# keypad-encoder.net
KiCad netlist of a schematic drawn in EAGLE
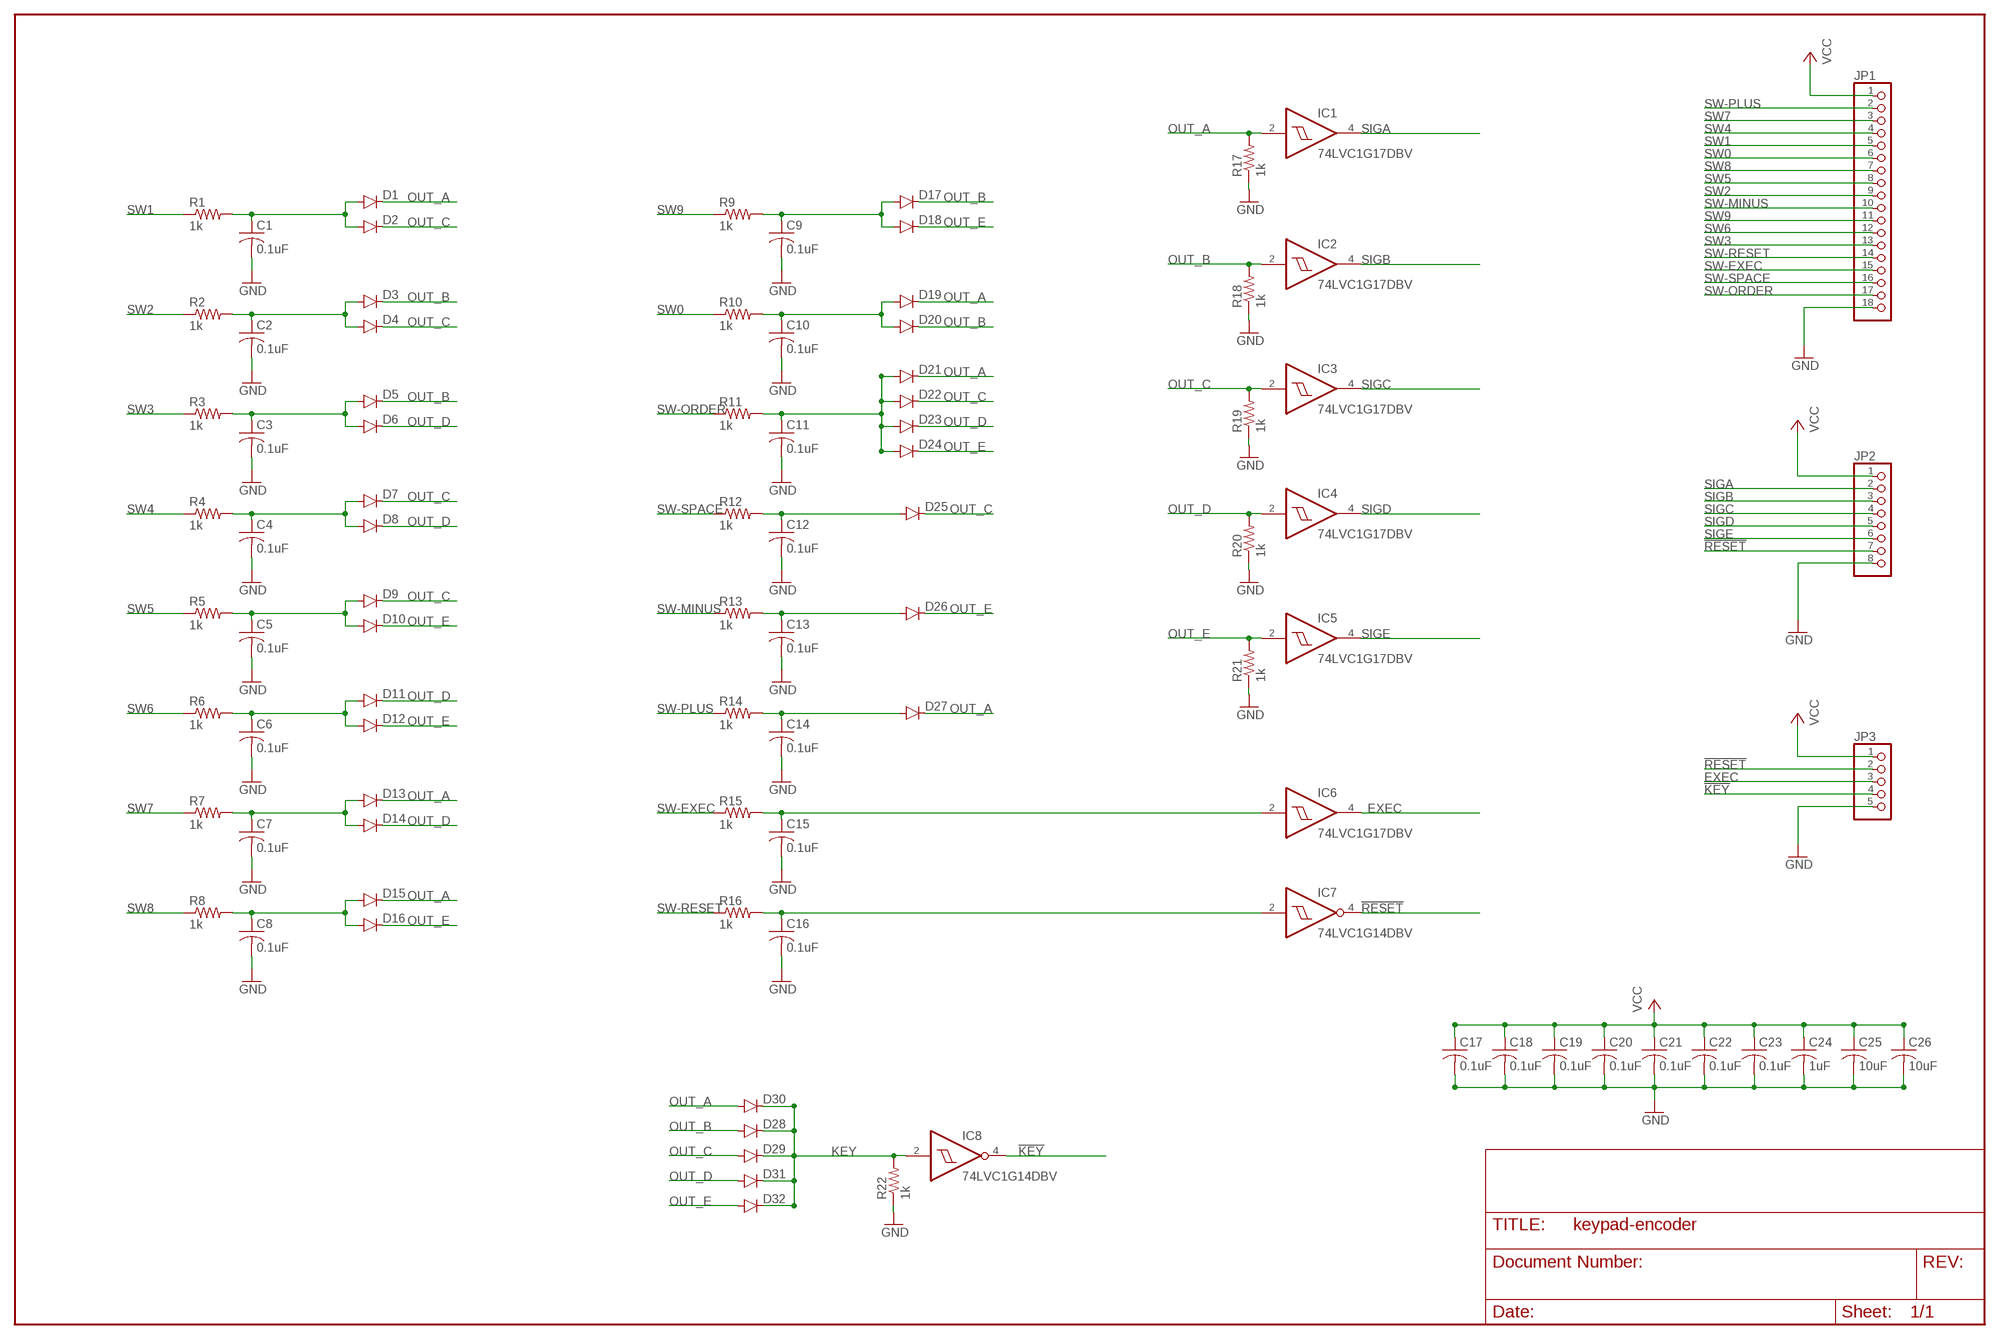
[diagram p0: schematic, sheet 1]

(export (version "E")
  (design (tool "Eeschema 10.0.6"))
  (components
    (comp (ref "C1")
      (value "0.1uF")
      (footprint "eagle-import:C0805")
      (libsource (lib "eagle-import") (part "C-USC0805"))
    )
    (comp (ref "C2")
      (value "0.1uF")
      (footprint "eagle-import:C0805")
      (libsource (lib "eagle-import") (part "C-USC0805"))
    )
    (comp (ref "C3")
      (value "0.1uF")
      (footprint "eagle-import:C0805")
      (libsource (lib "eagle-import") (part "C-USC0805"))
    )
    (comp (ref "C4")
      (value "0.1uF")
      (footprint "eagle-import:C0805")
      (libsource (lib "eagle-import") (part "C-USC0805"))
    )
    (comp (ref "C5")
      (value "0.1uF")
      (footprint "eagle-import:C0805")
      (libsource (lib "eagle-import") (part "C-USC0805"))
    )
    (comp (ref "C6")
      (value "0.1uF")
      (footprint "eagle-import:C0805")
      (libsource (lib "eagle-import") (part "C-USC0805"))
    )
    (comp (ref "C7")
      (value "0.1uF")
      (footprint "eagle-import:C0805")
      (libsource (lib "eagle-import") (part "C-USC0805"))
    )
    (comp (ref "C8")
      (value "0.1uF")
      (footprint "eagle-import:C0805")
      (libsource (lib "eagle-import") (part "C-USC0805"))
    )
    (comp (ref "C9")
      (value "0.1uF")
      (footprint "eagle-import:C0805")
      (libsource (lib "eagle-import") (part "C-USC0805"))
    )
    (comp (ref "C10")
      (value "0.1uF")
      (footprint "eagle-import:C0805")
      (libsource (lib "eagle-import") (part "C-USC0805"))
    )
    (comp (ref "C11")
      (value "0.1uF")
      (footprint "eagle-import:C0805")
      (libsource (lib "eagle-import") (part "C-USC0805"))
    )
    (comp (ref "C12")
      (value "0.1uF")
      (footprint "eagle-import:C0805")
      (libsource (lib "eagle-import") (part "C-USC0805"))
    )
    (comp (ref "C13")
      (value "0.1uF")
      (footprint "eagle-import:C0805")
      (libsource (lib "eagle-import") (part "C-USC0805"))
    )
    (comp (ref "C14")
      (value "0.1uF")
      (footprint "eagle-import:C0805")
      (libsource (lib "eagle-import") (part "C-USC0805"))
    )
    (comp (ref "C15")
      (value "0.1uF")
      (footprint "eagle-import:C0805")
      (libsource (lib "eagle-import") (part "C-USC0805"))
    )
    (comp (ref "C16")
      (value "0.1uF")
      (footprint "eagle-import:C0805")
      (libsource (lib "eagle-import") (part "C-USC0805"))
    )
    (comp (ref "C17")
      (value "0.1uF")
      (footprint "eagle-import:C0805")
      (libsource (lib "eagle-import") (part "C-USC0805"))
    )
    (comp (ref "C18")
      (value "0.1uF")
      (footprint "eagle-import:C0805")
      (libsource (lib "eagle-import") (part "C-USC0805"))
    )
    (comp (ref "C19")
      (value "0.1uF")
      (footprint "eagle-import:C0805")
      (libsource (lib "eagle-import") (part "C-USC0805"))
    )
    (comp (ref "C20")
      (value "0.1uF")
      (footprint "eagle-import:C0805")
      (libsource (lib "eagle-import") (part "C-USC0805"))
    )
    (comp (ref "C21")
      (value "0.1uF")
      (footprint "eagle-import:C0805")
      (libsource (lib "eagle-import") (part "C-USC0805"))
    )
    (comp (ref "C22")
      (value "0.1uF")
      (footprint "eagle-import:C0805")
      (libsource (lib "eagle-import") (part "C-USC0805"))
    )
    (comp (ref "C23")
      (value "0.1uF")
      (footprint "eagle-import:C0805")
      (libsource (lib "eagle-import") (part "C-USC0805"))
    )
    (comp (ref "C24")
      (value "1uF")
      (footprint "eagle-import:C0805")
      (libsource (lib "eagle-import") (part "C-USC0805"))
    )
    (comp (ref "C25")
      (value "10uF")
      (footprint "eagle-import:C0805")
      (libsource (lib "eagle-import") (part "C-USC0805"))
    )
    (comp (ref "C26")
      (value "10uF")
      (footprint "eagle-import:C0805")
      (libsource (lib "eagle-import") (part "C-USC0805"))
    )
    (comp (ref "D1")
      (value "DIODEPTH")
      (footprint "eagle-import:DIODE-1N4001")
      (libsource (lib "eagle-import") (part "DIODEPTH"))
    )
    (comp (ref "D2")
      (value "DIODEPTH")
      (footprint "eagle-import:DIODE-1N4001")
      (libsource (lib "eagle-import") (part "DIODEPTH"))
    )
    (comp (ref "D3")
      (value "DIODEPTH")
      (footprint "eagle-import:DIODE-1N4001")
      (libsource (lib "eagle-import") (part "DIODEPTH"))
    )
    (comp (ref "D4")
      (value "DIODEPTH")
      (footprint "eagle-import:DIODE-1N4001")
      (libsource (lib "eagle-import") (part "DIODEPTH"))
    )
    (comp (ref "D5")
      (value "DIODEPTH")
      (footprint "eagle-import:DIODE-1N4001")
      (libsource (lib "eagle-import") (part "DIODEPTH"))
    )
    (comp (ref "D6")
      (value "DIODEPTH")
      (footprint "eagle-import:DIODE-1N4001")
      (libsource (lib "eagle-import") (part "DIODEPTH"))
    )
    (comp (ref "D7")
      (value "DIODEPTH")
      (footprint "eagle-import:DIODE-1N4001")
      (libsource (lib "eagle-import") (part "DIODEPTH"))
    )
    (comp (ref "D8")
      (value "DIODEPTH")
      (footprint "eagle-import:DIODE-1N4001")
      (libsource (lib "eagle-import") (part "DIODEPTH"))
    )
    (comp (ref "D9")
      (value "DIODEPTH")
      (footprint "eagle-import:DIODE-1N4001")
      (libsource (lib "eagle-import") (part "DIODEPTH"))
    )
    (comp (ref "D10")
      (value "DIODEPTH")
      (footprint "eagle-import:DIODE-1N4001")
      (libsource (lib "eagle-import") (part "DIODEPTH"))
    )
    (comp (ref "D11")
      (value "DIODEPTH")
      (footprint "eagle-import:DIODE-1N4001")
      (libsource (lib "eagle-import") (part "DIODEPTH"))
    )
    (comp (ref "D12")
      (value "DIODEPTH")
      (footprint "eagle-import:DIODE-1N4001")
      (libsource (lib "eagle-import") (part "DIODEPTH"))
    )
    (comp (ref "D13")
      (value "DIODEPTH")
      (footprint "eagle-import:DIODE-1N4001")
      (libsource (lib "eagle-import") (part "DIODEPTH"))
    )
    (comp (ref "D14")
      (value "DIODEPTH")
      (footprint "eagle-import:DIODE-1N4001")
      (libsource (lib "eagle-import") (part "DIODEPTH"))
    )
    (comp (ref "D15")
      (value "DIODEPTH")
      (footprint "eagle-import:DIODE-1N4001")
      (libsource (lib "eagle-import") (part "DIODEPTH"))
    )
    (comp (ref "D16")
      (value "DIODEPTH")
      (footprint "eagle-import:DIODE-1N4001")
      (libsource (lib "eagle-import") (part "DIODEPTH"))
    )
    (comp (ref "D17")
      (value "DIODEPTH")
      (footprint "eagle-import:DIODE-1N4001")
      (libsource (lib "eagle-import") (part "DIODEPTH"))
    )
    (comp (ref "D18")
      (value "DIODEPTH")
      (footprint "eagle-import:DIODE-1N4001")
      (libsource (lib "eagle-import") (part "DIODEPTH"))
    )
    (comp (ref "D19")
      (value "DIODEPTH")
      (footprint "eagle-import:DIODE-1N4001")
      (libsource (lib "eagle-import") (part "DIODEPTH"))
    )
    (comp (ref "D20")
      (value "DIODEPTH")
      (footprint "eagle-import:DIODE-1N4001")
      (libsource (lib "eagle-import") (part "DIODEPTH"))
    )
    (comp (ref "D21")
      (value "DIODEPTH")
      (footprint "eagle-import:DIODE-1N4001")
      (libsource (lib "eagle-import") (part "DIODEPTH"))
    )
    (comp (ref "D22")
      (value "DIODEPTH")
      (footprint "eagle-import:DIODE-1N4001")
      (libsource (lib "eagle-import") (part "DIODEPTH"))
    )
    (comp (ref "D23")
      (value "DIODEPTH")
      (footprint "eagle-import:DIODE-1N4001")
      (libsource (lib "eagle-import") (part "DIODEPTH"))
    )
    (comp (ref "D24")
      (value "DIODEPTH")
      (footprint "eagle-import:DIODE-1N4001")
      (libsource (lib "eagle-import") (part "DIODEPTH"))
    )
    (comp (ref "D25")
      (value "DIODEPTH")
      (footprint "eagle-import:DIODE-1N4001")
      (libsource (lib "eagle-import") (part "DIODEPTH"))
    )
    (comp (ref "D26")
      (value "DIODEPTH")
      (footprint "eagle-import:DIODE-1N4001")
      (libsource (lib "eagle-import") (part "DIODEPTH"))
    )
    (comp (ref "D27")
      (value "DIODEPTH")
      (footprint "eagle-import:DIODE-1N4001")
      (libsource (lib "eagle-import") (part "DIODEPTH"))
    )
    (comp (ref "D28")
      (value "DIODEPTH")
      (footprint "eagle-import:DIODE-1N4001")
      (libsource (lib "eagle-import") (part "DIODEPTH"))
    )
    (comp (ref "D29")
      (value "DIODEPTH")
      (footprint "eagle-import:DIODE-1N4001")
      (libsource (lib "eagle-import") (part "DIODEPTH"))
    )
    (comp (ref "D30")
      (value "DIODEPTH")
      (footprint "eagle-import:DIODE-1N4001")
      (libsource (lib "eagle-import") (part "DIODEPTH"))
    )
    (comp (ref "D31")
      (value "DIODEPTH")
      (footprint "eagle-import:DIODE-1N4001")
      (libsource (lib "eagle-import") (part "DIODEPTH"))
    )
    (comp (ref "D32")
      (value "DIODEPTH")
      (footprint "eagle-import:DIODE-1N4001")
      (libsource (lib "eagle-import") (part "DIODEPTH"))
    )
    (comp (ref "IC1")
      (value "74LVC1G17DBV")
      (footprint "eagle-import:SOT23-5")
      (libsource (lib "eagle-import") (part "741G17DBVLVC"))
    )
    (comp (ref "IC2")
      (value "74LVC1G17DBV")
      (footprint "eagle-import:SOT23-5")
      (libsource (lib "eagle-import") (part "741G17DBVLVC"))
    )
    (comp (ref "IC3")
      (value "74LVC1G17DBV")
      (footprint "eagle-import:SOT23-5")
      (libsource (lib "eagle-import") (part "741G17DBVLVC"))
    )
    (comp (ref "IC4")
      (value "74LVC1G17DBV")
      (footprint "eagle-import:SOT23-5")
      (libsource (lib "eagle-import") (part "741G17DBVLVC"))
    )
    (comp (ref "IC5")
      (value "74LVC1G17DBV")
      (footprint "eagle-import:SOT23-5")
      (libsource (lib "eagle-import") (part "741G17DBVLVC"))
    )
    (comp (ref "IC6")
      (value "74LVC1G17DBV")
      (footprint "eagle-import:SOT23-5")
      (libsource (lib "eagle-import") (part "741G17DBVLVC"))
    )
    (comp (ref "IC7")
      (value "74LVC1G14DBV")
      (footprint "eagle-import:SOT23-5")
      (libsource (lib "eagle-import") (part "741G14DBVLVC"))
    )
    (comp (ref "IC8")
      (value "74LVC1G14DBV")
      (footprint "eagle-import:SOT23-5")
      (libsource (lib "eagle-import") (part "741G14DBVLVC"))
    )
    (comp (ref "JP1")
      (value "PINHD-1X18")
      (footprint "eagle-import:1X18")
      (libsource (lib "eagle-import") (part "PINHD-1X18"))
    )
    (comp (ref "JP2")
      (value "PINHD-1X8")
      (footprint "eagle-import:1X08")
      (libsource (lib "eagle-import") (part "PINHD-1X8"))
    )
    (comp (ref "JP3")
      (value "PINHD-1X5")
      (footprint "eagle-import:1X05")
      (libsource (lib "eagle-import") (part "PINHD-1X5"))
    )
    (comp (ref "R1")
      (value "1k")
      (footprint "eagle-import:R0805")
      (libsource (lib "eagle-import") (part "R-US_R0805"))
    )
    (comp (ref "R2")
      (value "1k")
      (footprint "eagle-import:R0805")
      (libsource (lib "eagle-import") (part "R-US_R0805"))
    )
    (comp (ref "R3")
      (value "1k")
      (footprint "eagle-import:R0805")
      (libsource (lib "eagle-import") (part "R-US_R0805"))
    )
    (comp (ref "R4")
      (value "1k")
      (footprint "eagle-import:R0805")
      (libsource (lib "eagle-import") (part "R-US_R0805"))
    )
    (comp (ref "R5")
      (value "1k")
      (footprint "eagle-import:R0805")
      (libsource (lib "eagle-import") (part "R-US_R0805"))
    )
    (comp (ref "R6")
      (value "1k")
      (footprint "eagle-import:R0805")
      (libsource (lib "eagle-import") (part "R-US_R0805"))
    )
    (comp (ref "R7")
      (value "1k")
      (footprint "eagle-import:R0805")
      (libsource (lib "eagle-import") (part "R-US_R0805"))
    )
    (comp (ref "R8")
      (value "1k")
      (footprint "eagle-import:R0805")
      (libsource (lib "eagle-import") (part "R-US_R0805"))
    )
    (comp (ref "R9")
      (value "1k")
      (footprint "eagle-import:R0805")
      (libsource (lib "eagle-import") (part "R-US_R0805"))
    )
    (comp (ref "R10")
      (value "1k")
      (footprint "eagle-import:R0805")
      (libsource (lib "eagle-import") (part "R-US_R0805"))
    )
    (comp (ref "R11")
      (value "1k")
      (footprint "eagle-import:R0805")
      (libsource (lib "eagle-import") (part "R-US_R0805"))
    )
    (comp (ref "R12")
      (value "1k")
      (footprint "eagle-import:R0805")
      (libsource (lib "eagle-import") (part "R-US_R0805"))
    )
    (comp (ref "R13")
      (value "1k")
      (footprint "eagle-import:R0805")
      (libsource (lib "eagle-import") (part "R-US_R0805"))
    )
    (comp (ref "R14")
      (value "1k")
      (footprint "eagle-import:R0805")
      (libsource (lib "eagle-import") (part "R-US_R0805"))
    )
    (comp (ref "R15")
      (value "1k")
      (footprint "eagle-import:R0805")
      (libsource (lib "eagle-import") (part "R-US_R0805"))
    )
    (comp (ref "R16")
      (value "1k")
      (footprint "eagle-import:R0805")
      (libsource (lib "eagle-import") (part "R-US_R0805"))
    )
    (comp (ref "R17")
      (value "1k")
      (footprint "eagle-import:R0805")
      (libsource (lib "eagle-import") (part "R-US_R0805"))
    )
    (comp (ref "R18")
      (value "1k")
      (footprint "eagle-import:R0805")
      (libsource (lib "eagle-import") (part "R-US_R0805"))
    )
    (comp (ref "R19")
      (value "1k")
      (footprint "eagle-import:R0805")
      (libsource (lib "eagle-import") (part "R-US_R0805"))
    )
    (comp (ref "R20")
      (value "1k")
      (footprint "eagle-import:R0805")
      (libsource (lib "eagle-import") (part "R-US_R0805"))
    )
    (comp (ref "R21")
      (value "1k")
      (footprint "eagle-import:R0805")
      (libsource (lib "eagle-import") (part "R-US_R0805"))
    )
    (comp (ref "R22")
      (value "1k")
      (footprint "eagle-import:R0805")
      (libsource (lib "eagle-import") (part "R-US_R0805"))
    )
  )
  (nets
    (net (code "1") (name "/EXEC") (class "Default")
      (node (ref "IC6") (pin "4") (pinfunction "O_4") (pintype "output"))
      (node (ref "JP3") (pin "3") (pinfunction "3_3") (pintype "passive"))
    )
    (net (code "2") (name "/KEY") (class "Default")
      (node (ref "D28") (pin "C") (pinfunction "C_C") (pintype "passive"))
      (node (ref "D29") (pin "C") (pinfunction "C_C") (pintype "passive"))
      (node (ref "D30") (pin "C") (pinfunction "C_C") (pintype "passive"))
      (node (ref "D31") (pin "C") (pinfunction "C_C") (pintype "passive"))
      (node (ref "D32") (pin "C") (pinfunction "C_C") (pintype "passive"))
      (node (ref "IC8") (pin "2") (pinfunction "I_2") (pintype "input"))
      (node (ref "R22") (pin "2") (pinfunction "2_2") (pintype "passive"))
    )
    (net (code "3") (name "/OUT_A") (class "Default")
      (node (ref "D1") (pin "C") (pinfunction "C_C") (pintype "passive"))
      (node (ref "D13") (pin "C") (pinfunction "C_C") (pintype "passive"))
      (node (ref "D15") (pin "C") (pinfunction "C_C") (pintype "passive"))
      (node (ref "D19") (pin "C") (pinfunction "C_C") (pintype "passive"))
      (node (ref "D21") (pin "C") (pinfunction "C_C") (pintype "passive"))
      (node (ref "D27") (pin "C") (pinfunction "C_C") (pintype "passive"))
      (node (ref "D30") (pin "A") (pinfunction "A_A") (pintype "passive"))
      (node (ref "IC1") (pin "2") (pinfunction "I_2") (pintype "input"))
      (node (ref "R17") (pin "2") (pinfunction "2_2") (pintype "passive"))
    )
    (net (code "4") (name "/OUT_B") (class "Default")
      (node (ref "D17") (pin "C") (pinfunction "C_C") (pintype "passive"))
      (node (ref "D20") (pin "C") (pinfunction "C_C") (pintype "passive"))
      (node (ref "D28") (pin "A") (pinfunction "A_A") (pintype "passive"))
      (node (ref "D3") (pin "C") (pinfunction "C_C") (pintype "passive"))
      (node (ref "D5") (pin "C") (pinfunction "C_C") (pintype "passive"))
      (node (ref "IC2") (pin "2") (pinfunction "I_2") (pintype "input"))
      (node (ref "R18") (pin "2") (pinfunction "2_2") (pintype "passive"))
    )
    (net (code "5") (name "/OUT_C") (class "Default")
      (node (ref "D2") (pin "C") (pinfunction "C_C") (pintype "passive"))
      (node (ref "D22") (pin "C") (pinfunction "C_C") (pintype "passive"))
      (node (ref "D25") (pin "C") (pinfunction "C_C") (pintype "passive"))
      (node (ref "D29") (pin "A") (pinfunction "A_A") (pintype "passive"))
      (node (ref "D4") (pin "C") (pinfunction "C_C") (pintype "passive"))
      (node (ref "D7") (pin "C") (pinfunction "C_C") (pintype "passive"))
      (node (ref "D9") (pin "C") (pinfunction "C_C") (pintype "passive"))
      (node (ref "IC3") (pin "2") (pinfunction "I_2") (pintype "input"))
      (node (ref "R19") (pin "2") (pinfunction "2_2") (pintype "passive"))
    )
    (net (code "6") (name "/OUT_D") (class "Default")
      (node (ref "D11") (pin "C") (pinfunction "C_C") (pintype "passive"))
      (node (ref "D14") (pin "C") (pinfunction "C_C") (pintype "passive"))
      (node (ref "D23") (pin "C") (pinfunction "C_C") (pintype "passive"))
      (node (ref "D31") (pin "A") (pinfunction "A_A") (pintype "passive"))
      (node (ref "D6") (pin "C") (pinfunction "C_C") (pintype "passive"))
      (node (ref "D8") (pin "C") (pinfunction "C_C") (pintype "passive"))
      (node (ref "IC4") (pin "2") (pinfunction "I_2") (pintype "input"))
      (node (ref "R20") (pin "2") (pinfunction "2_2") (pintype "passive"))
    )
    (net (code "7") (name "/OUT_E") (class "Default")
      (node (ref "D10") (pin "C") (pinfunction "C_C") (pintype "passive"))
      (node (ref "D12") (pin "C") (pinfunction "C_C") (pintype "passive"))
      (node (ref "D16") (pin "C") (pinfunction "C_C") (pintype "passive"))
      (node (ref "D18") (pin "C") (pinfunction "C_C") (pintype "passive"))
      (node (ref "D24") (pin "C") (pinfunction "C_C") (pintype "passive"))
      (node (ref "D26") (pin "C") (pinfunction "C_C") (pintype "passive"))
      (node (ref "D32") (pin "A") (pinfunction "A_A") (pintype "passive"))
      (node (ref "IC5") (pin "2") (pinfunction "I_2") (pintype "input"))
      (node (ref "R21") (pin "2") (pinfunction "2_2") (pintype "passive"))
    )
    (net (code "8") (name "/SIGA") (class "Default")
      (node (ref "IC1") (pin "4") (pinfunction "O_4") (pintype "output"))
      (node (ref "JP2") (pin "2") (pinfunction "2_2") (pintype "passive"))
    )
    (net (code "9") (name "/SIGB") (class "Default")
      (node (ref "IC2") (pin "4") (pinfunction "O_4") (pintype "output"))
      (node (ref "JP2") (pin "3") (pinfunction "3_3") (pintype "passive"))
    )
    (net (code "10") (name "/SIGC") (class "Default")
      (node (ref "IC3") (pin "4") (pinfunction "O_4") (pintype "output"))
      (node (ref "JP2") (pin "4") (pinfunction "4_4") (pintype "passive"))
    )
    (net (code "11") (name "/SIGD") (class "Default")
      (node (ref "IC4") (pin "4") (pinfunction "O_4") (pintype "output"))
      (node (ref "JP2") (pin "5") (pinfunction "5_5") (pintype "passive"))
    )
    (net (code "12") (name "/SIGE") (class "Default")
      (node (ref "IC5") (pin "4") (pinfunction "O_4") (pintype "output"))
      (node (ref "JP2") (pin "6") (pinfunction "6_6") (pintype "passive"))
    )
    (net (code "13") (name "/SW-EXEC") (class "Default")
      (node (ref "JP1") (pin "15") (pinfunction "15_15") (pintype "passive"))
      (node (ref "R15") (pin "1") (pinfunction "1_1") (pintype "passive"))
    )
    (net (code "14") (name "/SW-MINUS") (class "Default")
      (node (ref "JP1") (pin "10") (pinfunction "10_10") (pintype "passive"))
      (node (ref "R13") (pin "1") (pinfunction "1_1") (pintype "passive"))
    )
    (net (code "15") (name "/SW-ORDER") (class "Default")
      (node (ref "JP1") (pin "17") (pinfunction "17_17") (pintype "passive"))
      (node (ref "R11") (pin "1") (pinfunction "1_1") (pintype "passive"))
    )
    (net (code "16") (name "/SW-PLUS") (class "Default")
      (node (ref "JP1") (pin "2") (pinfunction "2_2") (pintype "passive"))
      (node (ref "R14") (pin "1") (pinfunction "1_1") (pintype "passive"))
    )
    (net (code "17") (name "/SW-RESET") (class "Default")
      (node (ref "JP1") (pin "14") (pinfunction "14_14") (pintype "passive"))
      (node (ref "R16") (pin "1") (pinfunction "1_1") (pintype "passive"))
    )
    (net (code "18") (name "/SW-SPACE") (class "Default")
      (node (ref "JP1") (pin "16") (pinfunction "16_16") (pintype "passive"))
      (node (ref "R12") (pin "1") (pinfunction "1_1") (pintype "passive"))
    )
    (net (code "19") (name "/SW0") (class "Default")
      (node (ref "JP1") (pin "6") (pinfunction "6_6") (pintype "passive"))
      (node (ref "R10") (pin "1") (pinfunction "1_1") (pintype "passive"))
    )
    (net (code "20") (name "/SW1") (class "Default")
      (node (ref "JP1") (pin "5") (pinfunction "5_5") (pintype "passive"))
      (node (ref "R1") (pin "1") (pinfunction "1_1") (pintype "passive"))
    )
    (net (code "21") (name "/SW2") (class "Default")
      (node (ref "JP1") (pin "9") (pinfunction "9_9") (pintype "passive"))
      (node (ref "R2") (pin "1") (pinfunction "1_1") (pintype "passive"))
    )
    (net (code "22") (name "/SW3") (class "Default")
      (node (ref "JP1") (pin "13") (pinfunction "13_13") (pintype "passive"))
      (node (ref "R3") (pin "1") (pinfunction "1_1") (pintype "passive"))
    )
    (net (code "23") (name "/SW4") (class "Default")
      (node (ref "JP1") (pin "4") (pinfunction "4_4") (pintype "passive"))
      (node (ref "R4") (pin "1") (pinfunction "1_1") (pintype "passive"))
    )
    (net (code "24") (name "/SW5") (class "Default")
      (node (ref "JP1") (pin "8") (pinfunction "8_8") (pintype "passive"))
      (node (ref "R5") (pin "1") (pinfunction "1_1") (pintype "passive"))
    )
    (net (code "25") (name "/SW6") (class "Default")
      (node (ref "JP1") (pin "12") (pinfunction "12_12") (pintype "passive"))
      (node (ref "R6") (pin "1") (pinfunction "1_1") (pintype "passive"))
    )
    (net (code "26") (name "/SW7") (class "Default")
      (node (ref "JP1") (pin "3") (pinfunction "3_3") (pintype "passive"))
      (node (ref "R7") (pin "1") (pinfunction "1_1") (pintype "passive"))
    )
    (net (code "27") (name "/SW8") (class "Default")
      (node (ref "JP1") (pin "7") (pinfunction "7_7") (pintype "passive"))
      (node (ref "R8") (pin "1") (pinfunction "1_1") (pintype "passive"))
    )
    (net (code "28") (name "/SW9") (class "Default")
      (node (ref "JP1") (pin "11") (pinfunction "11_11") (pintype "passive"))
      (node (ref "R9") (pin "1") (pinfunction "1_1") (pintype "passive"))
    )
    (net (code "29") (name "/~{KEY}") (class "Default")
      (node (ref "IC8") (pin "4") (pinfunction "O_4") (pintype "output"))
      (node (ref "JP3") (pin "4") (pinfunction "4_4") (pintype "passive"))
    )
    (net (code "30") (name "/~{RESET}") (class "Default")
      (node (ref "IC7") (pin "4") (pinfunction "O_4") (pintype "output"))
      (node (ref "JP2") (pin "7") (pinfunction "7_7") (pintype "passive"))
      (node (ref "JP3") (pin "2") (pinfunction "2_2") (pintype "passive"))
    )
    (net (code "31") (name "GND") (class "Default")
      (node (ref "C1") (pin "2") (pinfunction "2_2") (pintype "passive"))
      (node (ref "C10") (pin "2") (pinfunction "2_2") (pintype "passive"))
      (node (ref "C11") (pin "2") (pinfunction "2_2") (pintype "passive"))
      (node (ref "C12") (pin "2") (pinfunction "2_2") (pintype "passive"))
      (node (ref "C13") (pin "2") (pinfunction "2_2") (pintype "passive"))
      (node (ref "C14") (pin "2") (pinfunction "2_2") (pintype "passive"))
      (node (ref "C15") (pin "2") (pinfunction "2_2") (pintype "passive"))
      (node (ref "C16") (pin "2") (pinfunction "2_2") (pintype "passive"))
      (node (ref "C17") (pin "2") (pinfunction "2_2") (pintype "passive"))
      (node (ref "C18") (pin "2") (pinfunction "2_2") (pintype "passive"))
      (node (ref "C19") (pin "2") (pinfunction "2_2") (pintype "passive"))
      (node (ref "C2") (pin "2") (pinfunction "2_2") (pintype "passive"))
      (node (ref "C20") (pin "2") (pinfunction "2_2") (pintype "passive"))
      (node (ref "C21") (pin "2") (pinfunction "2_2") (pintype "passive"))
      (node (ref "C22") (pin "2") (pinfunction "2_2") (pintype "passive"))
      (node (ref "C23") (pin "2") (pinfunction "2_2") (pintype "passive"))
      (node (ref "C24") (pin "2") (pinfunction "2_2") (pintype "passive"))
      (node (ref "C25") (pin "2") (pinfunction "2_2") (pintype "passive"))
      (node (ref "C26") (pin "2") (pinfunction "2_2") (pintype "passive"))
      (node (ref "C3") (pin "2") (pinfunction "2_2") (pintype "passive"))
      (node (ref "C4") (pin "2") (pinfunction "2_2") (pintype "passive"))
      (node (ref "C5") (pin "2") (pinfunction "2_2") (pintype "passive"))
      (node (ref "C6") (pin "2") (pinfunction "2_2") (pintype "passive"))
      (node (ref "C7") (pin "2") (pinfunction "2_2") (pintype "passive"))
      (node (ref "C8") (pin "2") (pinfunction "2_2") (pintype "passive"))
      (node (ref "C9") (pin "2") (pinfunction "2_2") (pintype "passive"))
      (node (ref "JP1") (pin "18") (pinfunction "18_18") (pintype "passive"))
      (node (ref "JP2") (pin "8") (pinfunction "8_8") (pintype "passive"))
      (node (ref "JP3") (pin "5") (pinfunction "5_5") (pintype "passive"))
      (node (ref "R17") (pin "1") (pinfunction "1_1") (pintype "passive"))
      (node (ref "R18") (pin "1") (pinfunction "1_1") (pintype "passive"))
      (node (ref "R19") (pin "1") (pinfunction "1_1") (pintype "passive"))
      (node (ref "R20") (pin "1") (pinfunction "1_1") (pintype "passive"))
      (node (ref "R21") (pin "1") (pinfunction "1_1") (pintype "passive"))
      (node (ref "R22") (pin "1") (pinfunction "1_1") (pintype "passive"))
    )
    (net (code "32") (name "Net-(C1-Pad1)") (class "Default")
      (node (ref "C1") (pin "1") (pinfunction "1_1") (pintype "passive"))
      (node (ref "D1") (pin "A") (pinfunction "A_A") (pintype "passive"))
      (node (ref "D2") (pin "A") (pinfunction "A_A") (pintype "passive"))
      (node (ref "R1") (pin "2") (pinfunction "2_2") (pintype "passive"))
    )
    (net (code "33") (name "Net-(C2-Pad1)") (class "Default")
      (node (ref "C2") (pin "1") (pinfunction "1_1") (pintype "passive"))
      (node (ref "D3") (pin "A") (pinfunction "A_A") (pintype "passive"))
      (node (ref "D4") (pin "A") (pinfunction "A_A") (pintype "passive"))
      (node (ref "R2") (pin "2") (pinfunction "2_2") (pintype "passive"))
    )
    (net (code "34") (name "Net-(C3-Pad1)") (class "Default")
      (node (ref "C3") (pin "1") (pinfunction "1_1") (pintype "passive"))
      (node (ref "D5") (pin "A") (pinfunction "A_A") (pintype "passive"))
      (node (ref "D6") (pin "A") (pinfunction "A_A") (pintype "passive"))
      (node (ref "R3") (pin "2") (pinfunction "2_2") (pintype "passive"))
    )
    (net (code "35") (name "Net-(C4-Pad1)") (class "Default")
      (node (ref "C4") (pin "1") (pinfunction "1_1") (pintype "passive"))
      (node (ref "D7") (pin "A") (pinfunction "A_A") (pintype "passive"))
      (node (ref "D8") (pin "A") (pinfunction "A_A") (pintype "passive"))
      (node (ref "R4") (pin "2") (pinfunction "2_2") (pintype "passive"))
    )
    (net (code "36") (name "Net-(C5-Pad1)") (class "Default")
      (node (ref "C5") (pin "1") (pinfunction "1_1") (pintype "passive"))
      (node (ref "D10") (pin "A") (pinfunction "A_A") (pintype "passive"))
      (node (ref "D9") (pin "A") (pinfunction "A_A") (pintype "passive"))
      (node (ref "R5") (pin "2") (pinfunction "2_2") (pintype "passive"))
    )
    (net (code "37") (name "Net-(C6-Pad1)") (class "Default")
      (node (ref "C6") (pin "1") (pinfunction "1_1") (pintype "passive"))
      (node (ref "D11") (pin "A") (pinfunction "A_A") (pintype "passive"))
      (node (ref "D12") (pin "A") (pinfunction "A_A") (pintype "passive"))
      (node (ref "R6") (pin "2") (pinfunction "2_2") (pintype "passive"))
    )
    (net (code "38") (name "Net-(C7-Pad1)") (class "Default")
      (node (ref "C7") (pin "1") (pinfunction "1_1") (pintype "passive"))
      (node (ref "D13") (pin "A") (pinfunction "A_A") (pintype "passive"))
      (node (ref "D14") (pin "A") (pinfunction "A_A") (pintype "passive"))
      (node (ref "R7") (pin "2") (pinfunction "2_2") (pintype "passive"))
    )
    (net (code "39") (name "Net-(C8-Pad1)") (class "Default")
      (node (ref "C8") (pin "1") (pinfunction "1_1") (pintype "passive"))
      (node (ref "D15") (pin "A") (pinfunction "A_A") (pintype "passive"))
      (node (ref "D16") (pin "A") (pinfunction "A_A") (pintype "passive"))
      (node (ref "R8") (pin "2") (pinfunction "2_2") (pintype "passive"))
    )
    (net (code "40") (name "Net-(C9-Pad1)") (class "Default")
      (node (ref "C9") (pin "1") (pinfunction "1_1") (pintype "passive"))
      (node (ref "D17") (pin "A") (pinfunction "A_A") (pintype "passive"))
      (node (ref "D18") (pin "A") (pinfunction "A_A") (pintype "passive"))
      (node (ref "R9") (pin "2") (pinfunction "2_2") (pintype "passive"))
    )
    (net (code "41") (name "Net-(C10-Pad1)") (class "Default")
      (node (ref "C10") (pin "1") (pinfunction "1_1") (pintype "passive"))
      (node (ref "D19") (pin "A") (pinfunction "A_A") (pintype "passive"))
      (node (ref "D20") (pin "A") (pinfunction "A_A") (pintype "passive"))
      (node (ref "R10") (pin "2") (pinfunction "2_2") (pintype "passive"))
    )
    (net (code "42") (name "Net-(C11-Pad1)") (class "Default")
      (node (ref "C11") (pin "1") (pinfunction "1_1") (pintype "passive"))
      (node (ref "D21") (pin "A") (pinfunction "A_A") (pintype "passive"))
      (node (ref "D22") (pin "A") (pinfunction "A_A") (pintype "passive"))
      (node (ref "D23") (pin "A") (pinfunction "A_A") (pintype "passive"))
      (node (ref "D24") (pin "A") (pinfunction "A_A") (pintype "passive"))
      (node (ref "R11") (pin "2") (pinfunction "2_2") (pintype "passive"))
    )
    (net (code "43") (name "Net-(C12-Pad1)") (class "Default")
      (node (ref "C12") (pin "1") (pinfunction "1_1") (pintype "passive"))
      (node (ref "D25") (pin "A") (pinfunction "A_A") (pintype "passive"))
      (node (ref "R12") (pin "2") (pinfunction "2_2") (pintype "passive"))
    )
    (net (code "44") (name "Net-(C13-Pad1)") (class "Default")
      (node (ref "C13") (pin "1") (pinfunction "1_1") (pintype "passive"))
      (node (ref "D26") (pin "A") (pinfunction "A_A") (pintype "passive"))
      (node (ref "R13") (pin "2") (pinfunction "2_2") (pintype "passive"))
    )
    (net (code "45") (name "Net-(C14-Pad1)") (class "Default")
      (node (ref "C14") (pin "1") (pinfunction "1_1") (pintype "passive"))
      (node (ref "D27") (pin "A") (pinfunction "A_A") (pintype "passive"))
      (node (ref "R14") (pin "2") (pinfunction "2_2") (pintype "passive"))
    )
    (net (code "46") (name "Net-(IC6A-I)") (class "Default")
      (node (ref "C15") (pin "1") (pinfunction "1_1") (pintype "passive"))
      (node (ref "IC6") (pin "2") (pinfunction "I_2") (pintype "input"))
      (node (ref "R15") (pin "2") (pinfunction "2_2") (pintype "passive"))
    )
    (net (code "47") (name "Net-(IC7A-I)") (class "Default")
      (node (ref "C16") (pin "1") (pinfunction "1_1") (pintype "passive"))
      (node (ref "IC7") (pin "2") (pinfunction "I_2") (pintype "input"))
      (node (ref "R16") (pin "2") (pinfunction "2_2") (pintype "passive"))
    )
    (net (code "48") (name "VCC") (class "Default")
      (node (ref "C17") (pin "1") (pinfunction "1_1") (pintype "passive"))
      (node (ref "C18") (pin "1") (pinfunction "1_1") (pintype "passive"))
      (node (ref "C19") (pin "1") (pinfunction "1_1") (pintype "passive"))
      (node (ref "C20") (pin "1") (pinfunction "1_1") (pintype "passive"))
      (node (ref "C21") (pin "1") (pinfunction "1_1") (pintype "passive"))
      (node (ref "C22") (pin "1") (pinfunction "1_1") (pintype "passive"))
      (node (ref "C23") (pin "1") (pinfunction "1_1") (pintype "passive"))
      (node (ref "C24") (pin "1") (pinfunction "1_1") (pintype "passive"))
      (node (ref "C25") (pin "1") (pinfunction "1_1") (pintype "passive"))
      (node (ref "C26") (pin "1") (pinfunction "1_1") (pintype "passive"))
      (node (ref "JP1") (pin "1") (pinfunction "1_1") (pintype "passive"))
      (node (ref "JP2") (pin "1") (pinfunction "1_1") (pintype "passive"))
      (node (ref "JP3") (pin "1") (pinfunction "1_1") (pintype "passive"))
    )
  )
)
